# FPGAGTP.net
KiCad netlist of a schematic drawn in Altium Designer
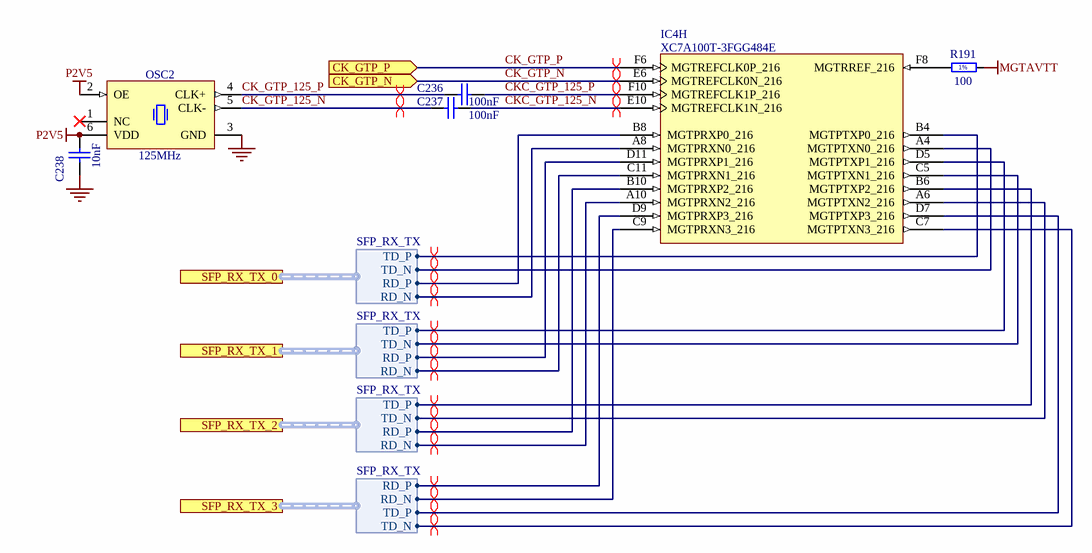
[diagram p0: FPGAGTP.SchDoc]

(export (version "E")
  (design (tool "Eeschema 10.0.6"))
  (components
    (comp (ref "C236")
      (value "100nF")
      (footprint "CAPC0603X33N")
      (description "Non-polarised capacitor")
      (fields
        (field (name "PART NUMBER") "CC0201_100NF_6.3V_10%_X5R")
        (field (name "VOLTAGE") "6.3V")
        (field (name "AUTHOR") "CERN DEM JLC")
      )
      (libsource (lib "Capacitors") (part "Capacitor - non polarized"))
    )
    (comp (ref "C237")
      (value "100nF")
      (footprint "CAPC0603X33N")
      (description "Non-polarised capacitor")
      (fields
        (field (name "PART NUMBER") "CC0201_100NF_6.3V_10%_X5R")
        (field (name "VOLTAGE") "6.3V")
        (field (name "AUTHOR") "CERN DEM JLC")
      )
      (libsource (lib "Capacitors") (part "Capacitor - non polarized"))
    )
    (comp (ref "C238")
      (value "10nF")
      (footprint "CAPC1005X55N")
      (description "Non-polarised capacitor")
      (fields
        (field (name "PART NUMBER") "CC0402_10NF_16V_10%_X7R")
        (field (name "VOLTAGE") "16V")
        (field (name "AUTHOR") "CERN DEM JLC")
      )
      (libsource (lib "Capacitors") (part "Capacitor - non polarized"))
    )
    (comp (ref "IC4")
      (value "XC7A100T-3FGG484E")
      (footprint "BGA484C100P22X22_2300X2300X260")
      (fields (field (name "MANUFACTURER") "XILINX") (field (name "AUTHOR") "CERN DEM BC"))
      (libsource (lib "ICs And Semiconductors") (part "XC7A100T-3FGG484E"))
    )
    (comp (ref "OSC2")
      (value "125MHz")
      (footprint "OSC_SILICON-LAB_SI510-6N")
      (description "Crystal Oscillator 6 pins, Si510 (LVDS/LVPECL/HCSL/Dual CMOS)")
      (fields
        (field (name "PART NUMBER") "OSC_125MHZ_SILICON-LAB_510FBA125M000AAG")
        (field (name "MANUFACTURER") "SILICON LABS")
        (field (name "AUTHOR") "CERN DEM JMW")
      )
      (libsource (lib "ICs And Semiconductors") (part "Oscillator SILICON-LAB_Si510-6N"))
    )
    (comp (ref "R191")
      (value "100")
      (footprint "RESC1005X40N")
      (description "Resistor - 1%")
      (fields
        (field (name "PART NUMBER") "R0402_100R_1%_0.0625W_100PPM")
        (field (name "POWER") "0.0625W")
        (field (name "AUTHOR") "CERN DEM JLC")
      )
      (libsource (lib "Resistors") (part "Resistor - 1%"))
    )
  )
  (nets
    (net (code "2") (name "/CKC_GTP_125_N") (class "Default")
      (node (ref "C237") (pin "2") (pinfunction "2_2") (pintype "passive"))
      (node (ref "IC4") (pin "E10") (pinfunction "MGTREFCLK1N_216_E10") (pintype "input"))
    )
    (net (code "3") (name "/CKC_GTP_125_P") (class "Default")
      (node (ref "C236") (pin "2") (pinfunction "2_2") (pintype "passive"))
      (node (ref "IC4") (pin "F10") (pinfunction "MGTREFCLK1P_216_F10") (pintype "input"))
    )
    (net (code "4") (name "/CK_GTP_125_N") (class "Default")
      (node (ref "C237") (pin "1") (pinfunction "1_1") (pintype "passive"))
      (node (ref "OSC2") (pin "5") (pinfunction "CLK-_5") (pintype "output"))
    )
    (net (code "5") (name "/CK_GTP_125_P") (class "Default")
      (node (ref "C236") (pin "1") (pinfunction "1_1") (pintype "passive"))
      (node (ref "OSC2") (pin "4") (pinfunction "CLK+_4") (pintype "output"))
    )
    (net (code "6") (name "/CK_GTP_N") (class "Default")
      (node (ref "IC4") (pin "E6") (pinfunction "MGTREFCLK0N_216_E6") (pintype "input"))
    )
    (net (code "7") (name "/CK_GTP_P") (class "Default")
      (node (ref "IC4") (pin "F6") (pinfunction "MGTREFCLK0P_216_F6") (pintype "input"))
    )
    (net (code "9") (name "GND") (class "Default")
      (node (ref "C238") (pin "1") (pinfunction "1_1") (pintype "passive"))
      (node (ref "OSC2") (pin "3") (pinfunction "GND_3") (pintype "power_in"))
    )
    (net (code "10") (name "MGTAVTT") (class "Default")
      (node (ref "R191") (pin "1") (pinfunction "1_1") (pintype "passive"))
    )
    (net (code "11") (name "Net-(IC4H-MGTRREF_216)") (class "Default")
      (node (ref "IC4") (pin "F8") (pinfunction "MGTRREF_216_F8") (pintype "input"))
      (node (ref "R191") (pin "2") (pinfunction "2_2") (pintype "passive"))
    )
    (net (code "12") (name "P2V5") (class "Default")
      (node (ref "C238") (pin "2") (pinfunction "2_2") (pintype "passive"))
      (node (ref "OSC2") (pin "2") (pinfunction "OE_2") (pintype "input"))
      (node (ref "OSC2") (pin "6") (pinfunction "VDD_6") (pintype "power_in"))
    )
    (net (code "13") (name "unconnected-(IC4H-MGTPRXN0_216-PadA8)") (class "Default")
      (node (ref "IC4") (pin "A8") (pinfunction "MGTPRXN0_216_A8") (pintype "input"))
    )
    (net (code "14") (name "unconnected-(IC4H-MGTPRXN1_216-PadC11)") (class "Default")
      (node (ref "IC4") (pin "C11") (pinfunction "MGTPRXN1_216_C11") (pintype "input"))
    )
    (net (code "15") (name "unconnected-(IC4H-MGTPRXN2_216-PadA10)") (class "Default")
      (node (ref "IC4") (pin "A10") (pinfunction "MGTPRXN2_216_A10") (pintype "input"))
    )
    (net (code "16") (name "unconnected-(IC4H-MGTPRXN3_216-PadC9)") (class "Default")
      (node (ref "IC4") (pin "C9") (pinfunction "MGTPRXN3_216_C9") (pintype "input"))
    )
    (net (code "17") (name "unconnected-(IC4H-MGTPRXP0_216-PadB8)") (class "Default")
      (node (ref "IC4") (pin "B8") (pinfunction "MGTPRXP0_216_B8") (pintype "input"))
    )
    (net (code "18") (name "unconnected-(IC4H-MGTPRXP1_216-PadD11)") (class "Default")
      (node (ref "IC4") (pin "D11") (pinfunction "MGTPRXP1_216_D11") (pintype "input"))
    )
    (net (code "19") (name "unconnected-(IC4H-MGTPRXP2_216-PadB10)") (class "Default")
      (node (ref "IC4") (pin "B10") (pinfunction "MGTPRXP2_216_B10") (pintype "input"))
    )
    (net (code "20") (name "unconnected-(IC4H-MGTPRXP3_216-PadD9)") (class "Default")
      (node (ref "IC4") (pin "D9") (pinfunction "MGTPRXP3_216_D9") (pintype "input"))
    )
    (net (code "21") (name "unconnected-(IC4H-MGTPTXN0_216-PadA4)") (class "Default")
      (node (ref "IC4") (pin "A4") (pinfunction "MGTPTXN0_216_A4") (pintype "output"))
    )
    (net (code "22") (name "unconnected-(IC4H-MGTPTXN1_216-PadC5)") (class "Default")
      (node (ref "IC4") (pin "C5") (pinfunction "MGTPTXN1_216_C5") (pintype "output"))
    )
    (net (code "23") (name "unconnected-(IC4H-MGTPTXN2_216-PadA6)") (class "Default")
      (node (ref "IC4") (pin "A6") (pinfunction "MGTPTXN2_216_A6") (pintype "output"))
    )
    (net (code "24") (name "unconnected-(IC4H-MGTPTXN3_216-PadC7)") (class "Default")
      (node (ref "IC4") (pin "C7") (pinfunction "MGTPTXN3_216_C7") (pintype "output"))
    )
    (net (code "25") (name "unconnected-(IC4H-MGTPTXP0_216-PadB4)") (class "Default")
      (node (ref "IC4") (pin "B4") (pinfunction "MGTPTXP0_216_B4") (pintype "output"))
    )
    (net (code "26") (name "unconnected-(IC4H-MGTPTXP1_216-PadD5)") (class "Default")
      (node (ref "IC4") (pin "D5") (pinfunction "MGTPTXP1_216_D5") (pintype "output"))
    )
    (net (code "27") (name "unconnected-(IC4H-MGTPTXP2_216-PadB6)") (class "Default")
      (node (ref "IC4") (pin "B6") (pinfunction "MGTPTXP2_216_B6") (pintype "output"))
    )
    (net (code "28") (name "unconnected-(IC4H-MGTPTXP3_216-PadD7)") (class "Default")
      (node (ref "IC4") (pin "D7") (pinfunction "MGTPTXP3_216_D7") (pintype "output"))
    )
    (net (code "29") (name "unconnected-(OSC2-NC-Pad1)") (class "Default")
      (node (ref "OSC2") (pin "1") (pinfunction "NC_1") (pintype "passive+no_connect"))
    )
  )
)
